# y.net
KiCad netlist of a schematic drawn in EAGLE
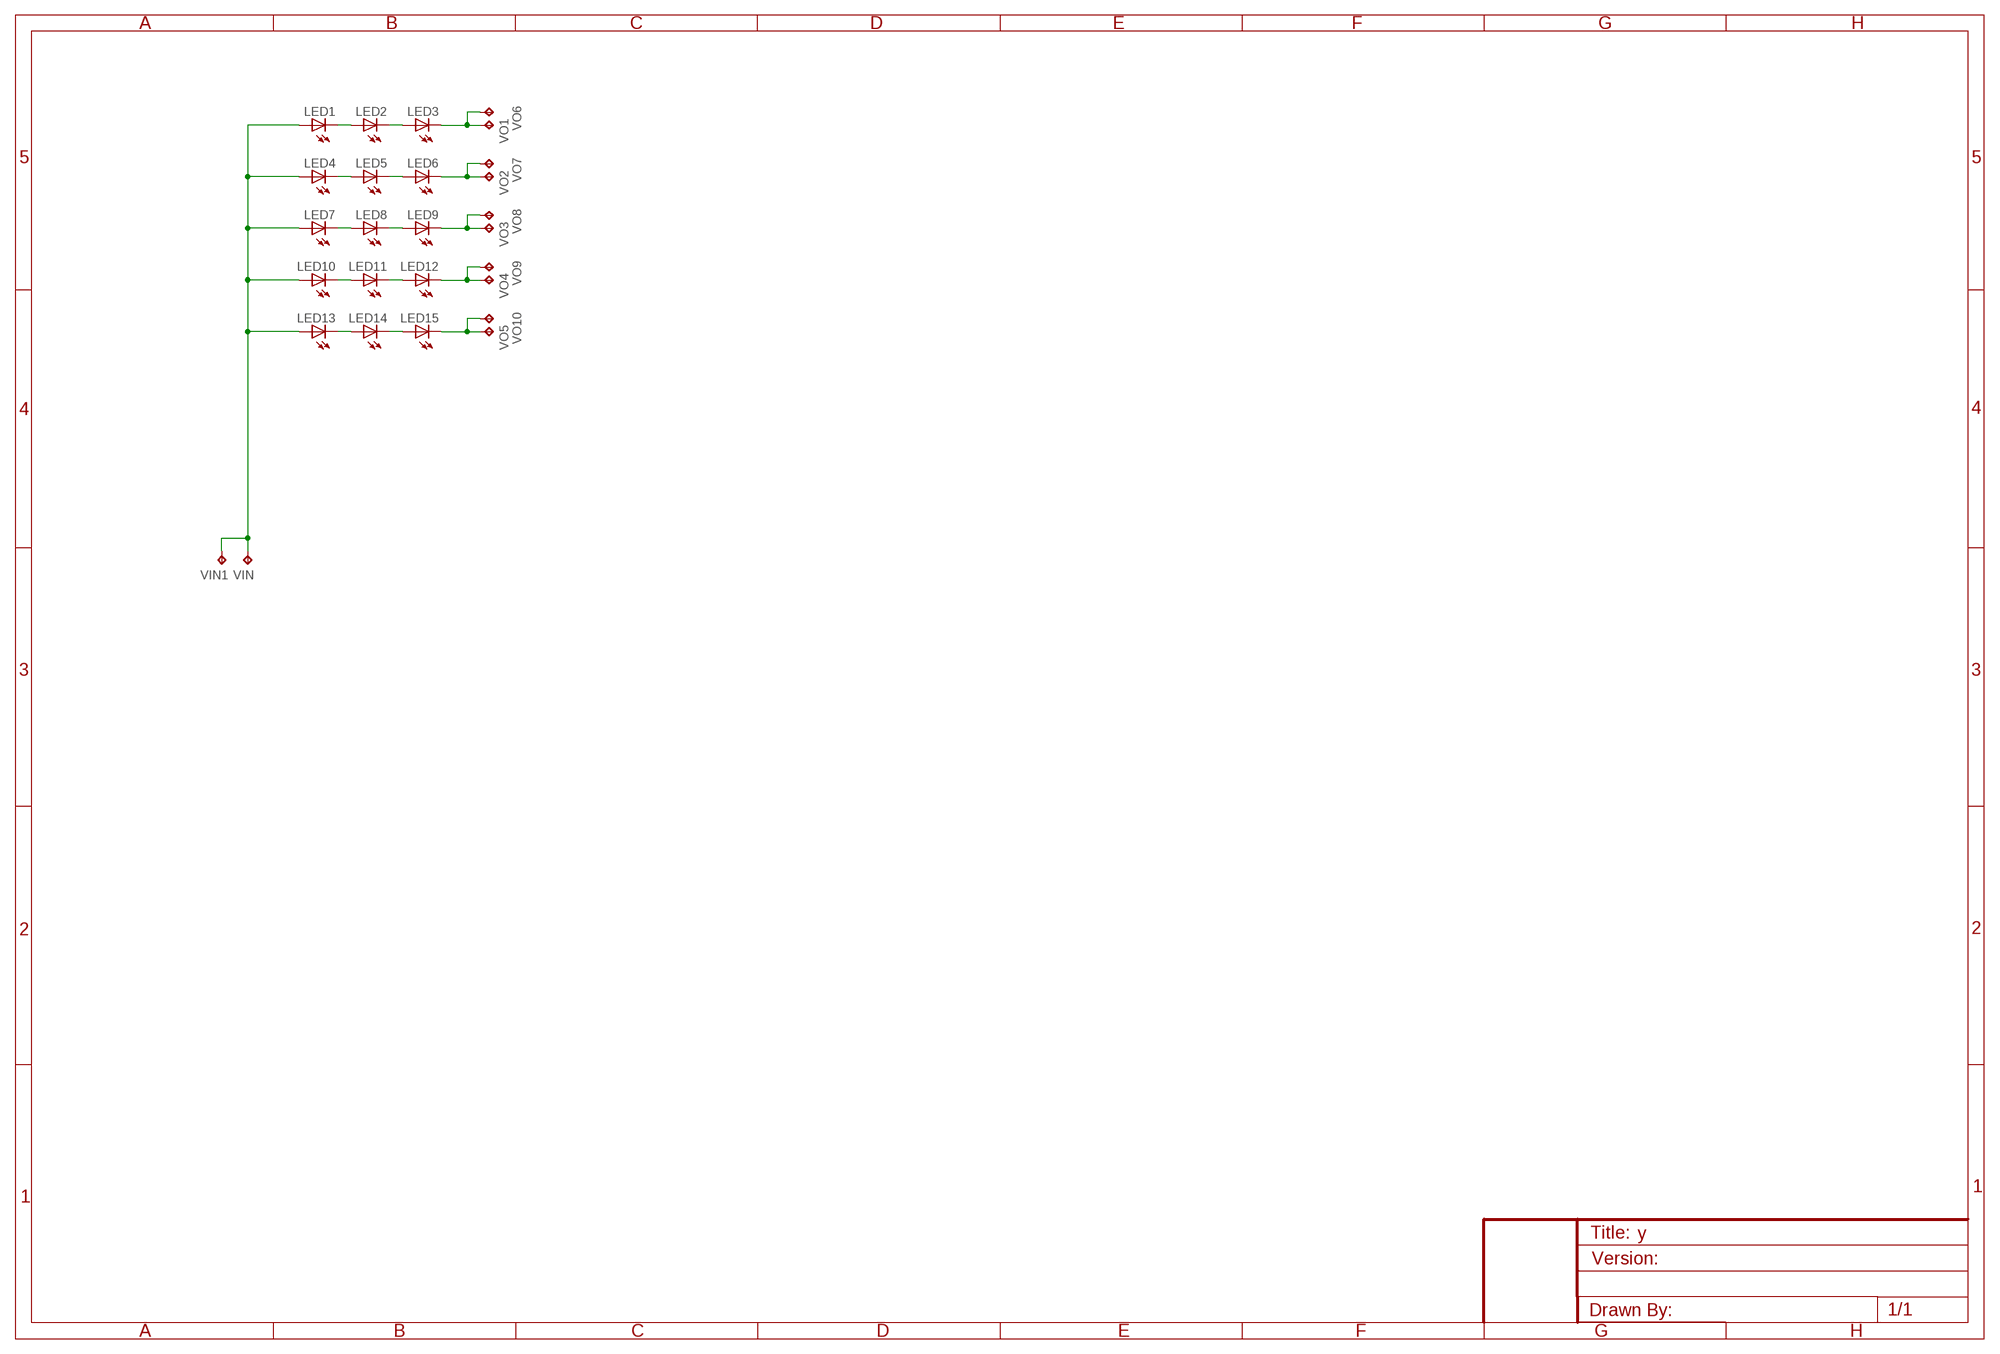
[diagram p0: schematic, sheet 1]

(export (version "E")
  (design (tool "Eeschema 10.0.6"))
  (components
    (comp (ref "LED1")
      (value "LED0805")
      (footprint "eagle-import:LED_0805")
      (libsource (lib "eagle-import") (part "LED0805"))
    )
    (comp (ref "LED2")
      (value "LED0805")
      (footprint "eagle-import:LED_0805")
      (libsource (lib "eagle-import") (part "LED0805"))
    )
    (comp (ref "LED3")
      (value "LED0805")
      (footprint "eagle-import:LED_0805")
      (libsource (lib "eagle-import") (part "LED0805"))
    )
    (comp (ref "LED4")
      (value "LED0805")
      (footprint "eagle-import:LED_0805")
      (libsource (lib "eagle-import") (part "LED0805"))
    )
    (comp (ref "LED5")
      (value "LED0805")
      (footprint "eagle-import:LED_0805")
      (libsource (lib "eagle-import") (part "LED0805"))
    )
    (comp (ref "LED6")
      (value "LED0805")
      (footprint "eagle-import:LED_0805")
      (libsource (lib "eagle-import") (part "LED0805"))
    )
    (comp (ref "LED7")
      (value "LED0805")
      (footprint "eagle-import:LED_0805")
      (libsource (lib "eagle-import") (part "LED0805"))
    )
    (comp (ref "LED8")
      (value "LED0805")
      (footprint "eagle-import:LED_0805")
      (libsource (lib "eagle-import") (part "LED0805"))
    )
    (comp (ref "LED9")
      (value "LED0805")
      (footprint "eagle-import:LED_0805")
      (libsource (lib "eagle-import") (part "LED0805"))
    )
    (comp (ref "LED10")
      (value "LED0805")
      (footprint "eagle-import:LED_0805")
      (libsource (lib "eagle-import") (part "LED0805"))
    )
    (comp (ref "LED11")
      (value "LED0805")
      (footprint "eagle-import:LED_0805")
      (libsource (lib "eagle-import") (part "LED0805"))
    )
    (comp (ref "LED12")
      (value "LED0805")
      (footprint "eagle-import:LED_0805")
      (libsource (lib "eagle-import") (part "LED0805"))
    )
    (comp (ref "LED13")
      (value "LED0805")
      (footprint "eagle-import:LED_0805")
      (libsource (lib "eagle-import") (part "LED0805"))
    )
    (comp (ref "LED14")
      (value "LED0805")
      (footprint "eagle-import:LED_0805")
      (libsource (lib "eagle-import") (part "LED0805"))
    )
    (comp (ref "LED15")
      (value "LED0805")
      (footprint "eagle-import:LED_0805")
      (libsource (lib "eagle-import") (part "LED0805"))
    )
    (comp (ref "VIN")
      (value "TEST_POINTPAD1-20")
      (footprint "eagle-import:P1-20")
      (libsource (lib "eagle-import") (part "TEST_POINTPAD1-20"))
    )
    (comp (ref "VIN1")
      (value "TEST_POINTPAD1-20")
      (footprint "eagle-import:P1-20")
      (libsource (lib "eagle-import") (part "TEST_POINTPAD1-20"))
    )
    (comp (ref "VO1")
      (value "TEST_POINTPAD1-20")
      (footprint "eagle-import:P1-20")
      (libsource (lib "eagle-import") (part "TEST_POINTPAD1-20"))
    )
    (comp (ref "VO2")
      (value "TEST_POINTPAD1-20")
      (footprint "eagle-import:P1-20")
      (libsource (lib "eagle-import") (part "TEST_POINTPAD1-20"))
    )
    (comp (ref "VO3")
      (value "TEST_POINTPAD1-20")
      (footprint "eagle-import:P1-20")
      (libsource (lib "eagle-import") (part "TEST_POINTPAD1-20"))
    )
    (comp (ref "VO4")
      (value "TEST_POINTPAD1-20")
      (footprint "eagle-import:P1-20")
      (libsource (lib "eagle-import") (part "TEST_POINTPAD1-20"))
    )
    (comp (ref "VO5")
      (value "TEST_POINTPAD1-20")
      (footprint "eagle-import:P1-20")
      (libsource (lib "eagle-import") (part "TEST_POINTPAD1-20"))
    )
    (comp (ref "VO6")
      (value "TEST_POINTPAD1-20")
      (footprint "eagle-import:P1-20")
      (libsource (lib "eagle-import") (part "TEST_POINTPAD1-20"))
    )
    (comp (ref "VO7")
      (value "TEST_POINTPAD1-20")
      (footprint "eagle-import:P1-20")
      (libsource (lib "eagle-import") (part "TEST_POINTPAD1-20"))
    )
    (comp (ref "VO8")
      (value "TEST_POINTPAD1-20")
      (footprint "eagle-import:P1-20")
      (libsource (lib "eagle-import") (part "TEST_POINTPAD1-20"))
    )
    (comp (ref "VO9")
      (value "TEST_POINTPAD1-20")
      (footprint "eagle-import:P1-20")
      (libsource (lib "eagle-import") (part "TEST_POINTPAD1-20"))
    )
    (comp (ref "VO10")
      (value "TEST_POINTPAD1-20")
      (footprint "eagle-import:P1-20")
      (libsource (lib "eagle-import") (part "TEST_POINTPAD1-20"))
    )
  )
  (nets
    (net (code "1") (name "Net-(LED1-PadA)") (class "Default")
      (node (ref "LED1") (pin "A") (pinfunction "A_A") (pintype "passive"))
      (node (ref "LED10") (pin "A") (pinfunction "A_A") (pintype "passive"))
      (node (ref "LED13") (pin "A") (pinfunction "A_A") (pintype "passive"))
      (node (ref "LED4") (pin "A") (pinfunction "A_A") (pintype "passive"))
      (node (ref "LED7") (pin "A") (pinfunction "A_A") (pintype "passive"))
      (node (ref "VIN") (pin "TP") (pinfunction "TP_TP") (pintype "input"))
      (node (ref "VIN1") (pin "TP") (pinfunction "TP_TP") (pintype "input"))
    )
    (net (code "2") (name "Net-(LED1-PadC)") (class "Default")
      (node (ref "LED1") (pin "C") (pinfunction "C_C") (pintype "passive"))
      (node (ref "LED2") (pin "A") (pinfunction "A_A") (pintype "passive"))
    )
    (net (code "3") (name "Net-(LED2-PadC)") (class "Default")
      (node (ref "LED2") (pin "C") (pinfunction "C_C") (pintype "passive"))
      (node (ref "LED3") (pin "A") (pinfunction "A_A") (pintype "passive"))
    )
    (net (code "4") (name "Net-(LED3-PadC)") (class "Default")
      (node (ref "LED3") (pin "C") (pinfunction "C_C") (pintype "passive"))
      (node (ref "VO1") (pin "TP") (pinfunction "TP_TP") (pintype "input"))
      (node (ref "VO6") (pin "TP") (pinfunction "TP_TP") (pintype "input"))
    )
    (net (code "5") (name "Net-(LED4-PadC)") (class "Default")
      (node (ref "LED4") (pin "C") (pinfunction "C_C") (pintype "passive"))
      (node (ref "LED5") (pin "A") (pinfunction "A_A") (pintype "passive"))
    )
    (net (code "6") (name "Net-(LED5-PadC)") (class "Default")
      (node (ref "LED5") (pin "C") (pinfunction "C_C") (pintype "passive"))
      (node (ref "LED6") (pin "A") (pinfunction "A_A") (pintype "passive"))
    )
    (net (code "7") (name "Net-(LED6-PadC)") (class "Default")
      (node (ref "LED6") (pin "C") (pinfunction "C_C") (pintype "passive"))
      (node (ref "VO2") (pin "TP") (pinfunction "TP_TP") (pintype "input"))
      (node (ref "VO7") (pin "TP") (pinfunction "TP_TP") (pintype "input"))
    )
    (net (code "8") (name "Net-(LED7-PadC)") (class "Default")
      (node (ref "LED7") (pin "C") (pinfunction "C_C") (pintype "passive"))
      (node (ref "LED8") (pin "A") (pinfunction "A_A") (pintype "passive"))
    )
    (net (code "9") (name "Net-(LED8-PadC)") (class "Default")
      (node (ref "LED8") (pin "C") (pinfunction "C_C") (pintype "passive"))
      (node (ref "LED9") (pin "A") (pinfunction "A_A") (pintype "passive"))
    )
    (net (code "10") (name "Net-(LED9-PadC)") (class "Default")
      (node (ref "LED9") (pin "C") (pinfunction "C_C") (pintype "passive"))
      (node (ref "VO3") (pin "TP") (pinfunction "TP_TP") (pintype "input"))
      (node (ref "VO8") (pin "TP") (pinfunction "TP_TP") (pintype "input"))
    )
    (net (code "11") (name "Net-(LED10-PadC)") (class "Default")
      (node (ref "LED10") (pin "C") (pinfunction "C_C") (pintype "passive"))
      (node (ref "LED11") (pin "A") (pinfunction "A_A") (pintype "passive"))
    )
    (net (code "12") (name "Net-(LED11-PadC)") (class "Default")
      (node (ref "LED11") (pin "C") (pinfunction "C_C") (pintype "passive"))
      (node (ref "LED12") (pin "A") (pinfunction "A_A") (pintype "passive"))
    )
    (net (code "13") (name "Net-(LED12-PadC)") (class "Default")
      (node (ref "LED12") (pin "C") (pinfunction "C_C") (pintype "passive"))
      (node (ref "VO4") (pin "TP") (pinfunction "TP_TP") (pintype "input"))
      (node (ref "VO9") (pin "TP") (pinfunction "TP_TP") (pintype "input"))
    )
    (net (code "14") (name "Net-(LED13-PadC)") (class "Default")
      (node (ref "LED13") (pin "C") (pinfunction "C_C") (pintype "passive"))
      (node (ref "LED14") (pin "A") (pinfunction "A_A") (pintype "passive"))
    )
    (net (code "15") (name "Net-(LED14-PadC)") (class "Default")
      (node (ref "LED14") (pin "C") (pinfunction "C_C") (pintype "passive"))
      (node (ref "LED15") (pin "A") (pinfunction "A_A") (pintype "passive"))
    )
    (net (code "16") (name "Net-(LED15-PadC)") (class "Default")
      (node (ref "LED15") (pin "C") (pinfunction "C_C") (pintype "passive"))
      (node (ref "VO10") (pin "TP") (pinfunction "TP_TP") (pintype "input"))
      (node (ref "VO5") (pin "TP") (pinfunction "TP_TP") (pintype "input"))
    )
  )
)
